# Sheet1.net
KiCad netlist of a schematic drawn in Altium Designer
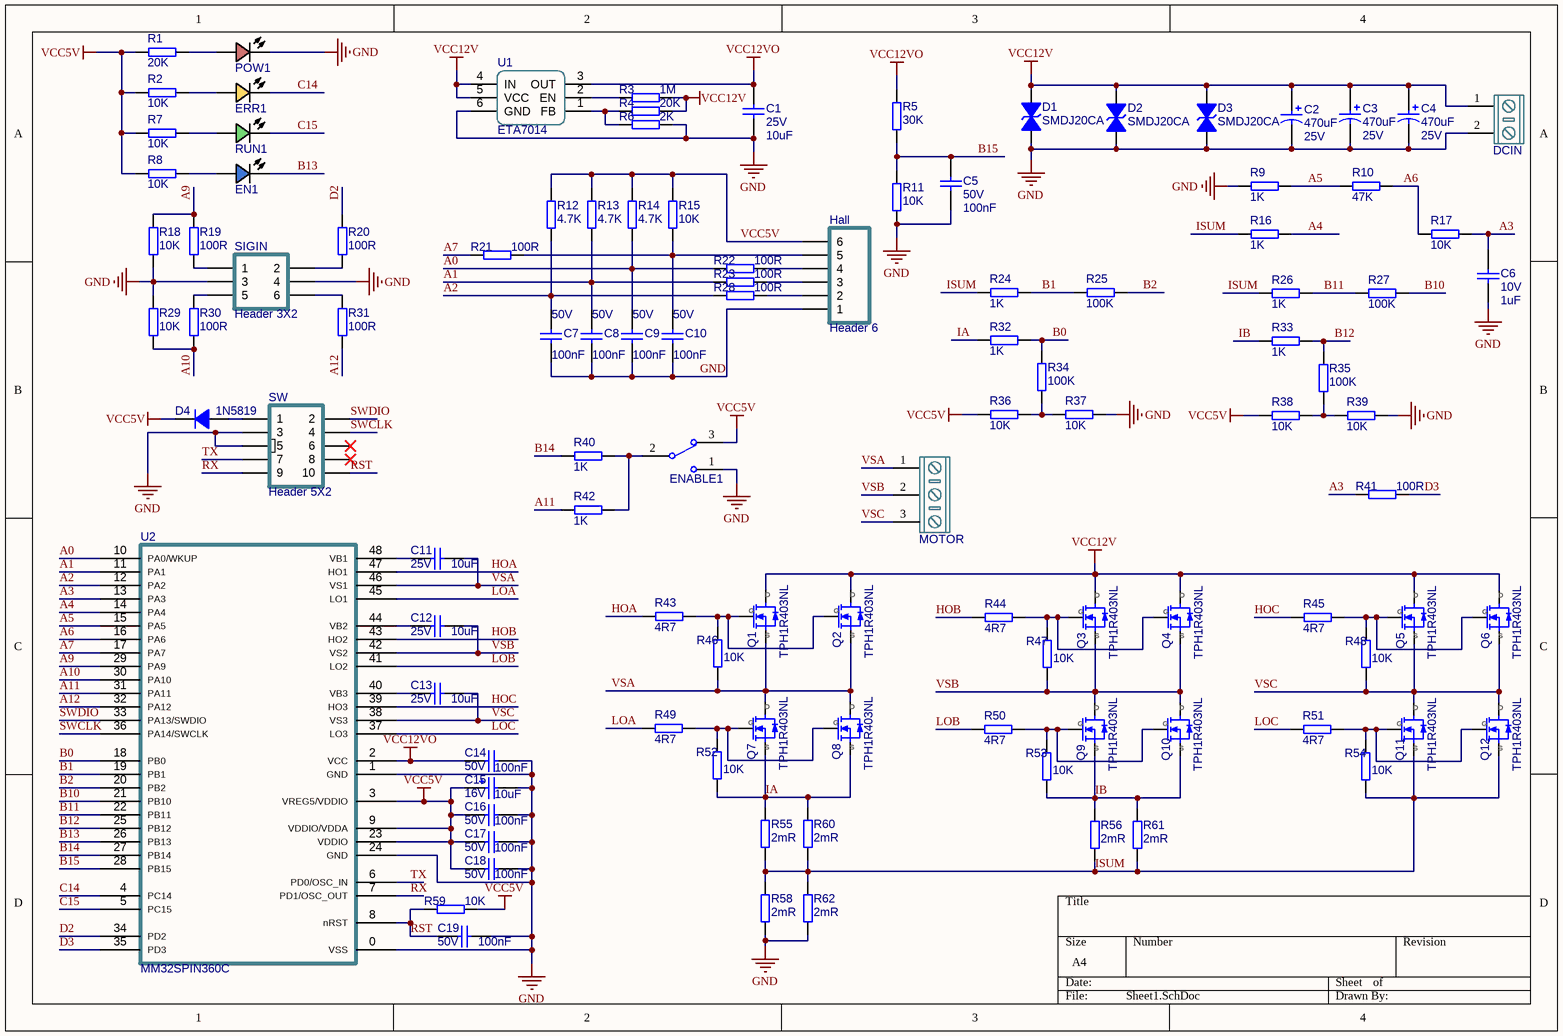
[diagram p0: Sheet1.SchDoc]

(export (version "E")
  (design (tool "Eeschema 10.0.6"))
  (components
    (comp (ref "C1")
      (value "10uF")
      (footprint "CAPC2012[0805]S-N")
      (description "贴片电容")
      (fields
        (field (name "TOLERANCE") "±10%")
        (field (name "VOLTAGE") "25V")
        (field (name "Comment") "10uF ±10% 25V")
      )
      (libsource (lib "无刷电调-MindMotion") (part "Cap-Chip"))
    )
    (comp (ref "C2")
      (value "470uF")
      (footprint "CAPPR3.5-8X12")
      (description "Polarized Capacitor (Radial)")
      (fields
        (field (name "VOLTAGE") "25V")
        (field (name "Comment") "470uF 25V")
        (field (name "PUBLISHER") "Altium Limited")
      )
      (libsource (lib "无刷电调-MindMotion") (part "Cap-Elect"))
    )
    (comp (ref "C3")
      (value "470uF")
      (footprint "CAPPR3.5-8X12")
      (description "Polarized Capacitor (Radial)")
      (fields
        (field (name "VOLTAGE") "25V")
        (field (name "Comment") "470uF 25V")
        (field (name "PUBLISHER") "Altium Limited")
      )
      (libsource (lib "无刷电调-MindMotion") (part "Cap-Elect"))
    )
    (comp (ref "C4")
      (value "470uF")
      (footprint "CAPPR3.5-8X12")
      (description "Polarized Capacitor (Radial)")
      (fields
        (field (name "VOLTAGE") "25V")
        (field (name "Comment") "470uF 25V")
        (field (name "PUBLISHER") "Altium Limited")
      )
      (libsource (lib "无刷电调-MindMotion") (part "Cap-Elect"))
    )
    (comp (ref "C5")
      (value "100nF")
      (footprint "CAPC2012[0805]S-N")
      (description "贴片电容")
      (fields
        (field (name "TOLERANCE") "±10%")
        (field (name "VOLTAGE") "50V")
        (field (name "Comment") "100nF ±10% 50V")
      )
      (libsource (lib "无刷电调-MindMotion") (part "Cap-Chip_1"))
    )
    (comp (ref "C6")
      (value "1uF")
      (footprint "CAPC2012[0805]S-N")
      (description "贴片电容")
      (fields
        (field (name "TOLERANCE") "±10%")
        (field (name "VOLTAGE") "10V")
        (field (name "Comment") "1uF ±10% 10V")
      )
      (libsource (lib "无刷电调-MindMotion") (part "Cap-Chip_2"))
    )
    (comp (ref "C7")
      (value "100nF")
      (footprint "CAPC2012[0805]S-N")
      (description "贴片电容")
      (fields
        (field (name "TOLERANCE") "±10%")
        (field (name "VOLTAGE") "50V")
        (field (name "Comment") "100nF ±10% 50V")
      )
      (libsource (lib "无刷电调-MindMotion") (part "Cap-Chip_1"))
    )
    (comp (ref "C8")
      (value "100nF")
      (footprint "CAPC2012[0805]S-N")
      (description "贴片电容")
      (fields
        (field (name "TOLERANCE") "±10%")
        (field (name "VOLTAGE") "50V")
        (field (name "Comment") "100nF ±10% 50V")
      )
      (libsource (lib "无刷电调-MindMotion") (part "Cap-Chip_1"))
    )
    (comp (ref "C9")
      (value "100nF")
      (footprint "CAPC2012[0805]S-N")
      (description "贴片电容")
      (fields
        (field (name "TOLERANCE") "±10%")
        (field (name "VOLTAGE") "50V")
        (field (name "Comment") "100nF ±10% 50V")
      )
      (libsource (lib "无刷电调-MindMotion") (part "Cap-Chip_1"))
    )
    (comp (ref "C10")
      (value "100nF")
      (footprint "CAPC2012[0805]S-N")
      (description "贴片电容")
      (fields
        (field (name "TOLERANCE") "±10%")
        (field (name "VOLTAGE") "50V")
        (field (name "Comment") "100nF ±10% 50V")
      )
      (libsource (lib "无刷电调-MindMotion") (part "Cap-Chip_1"))
    )
    (comp (ref "C11")
      (value "10uF")
      (footprint "CAPC2012[0805]S-N")
      (description "贴片电容")
      (fields
        (field (name "TOLERANCE") "±10%")
        (field (name "VOLTAGE") "25V")
        (field (name "Comment") "10uF ±10% 25V")
      )
      (libsource (lib "无刷电调-MindMotion") (part "Cap-Chip"))
    )
    (comp (ref "C12")
      (value "10uF")
      (footprint "CAPC2012[0805]S-N")
      (description "贴片电容")
      (fields
        (field (name "TOLERANCE") "±10%")
        (field (name "VOLTAGE") "25V")
        (field (name "Comment") "10uF ±10% 25V")
      )
      (libsource (lib "无刷电调-MindMotion") (part "Cap-Chip"))
    )
    (comp (ref "C13")
      (value "10uF")
      (footprint "CAPC2012[0805]S-N")
      (description "贴片电容")
      (fields
        (field (name "TOLERANCE") "±10%")
        (field (name "VOLTAGE") "25V")
        (field (name "Comment") "10uF ±10% 25V")
      )
      (libsource (lib "无刷电调-MindMotion") (part "Cap-Chip"))
    )
    (comp (ref "C14")
      (value "100nF")
      (footprint "CAPC2012[0805]S-N")
      (description "贴片电容")
      (fields
        (field (name "TOLERANCE") "±10%")
        (field (name "VOLTAGE") "50V")
        (field (name "Comment") "100nF ±10% 50V")
      )
      (libsource (lib "无刷电调-MindMotion") (part "Cap-Chip_1"))
    )
    (comp (ref "C15")
      (value "10uF")
      (footprint "CAPT3216")
      (description "Tantalum Capacitor")
      (fields
        (field (name "VOLTAGE") "16V")
        (field (name "Comment") "10uF 16V")
        (field (name "PUBLISHER") "Altium Limited")
      )
      (libsource (lib "无刷电调-MindMotion") (part "Cap-Tan"))
    )
    (comp (ref "C16")
      (value "100nF")
      (footprint "CAPC2012[0805]S-N")
      (description "贴片电容")
      (fields
        (field (name "TOLERANCE") "±10%")
        (field (name "VOLTAGE") "50V")
        (field (name "Comment") "100nF ±10% 50V")
      )
      (libsource (lib "无刷电调-MindMotion") (part "Cap-Chip_1"))
    )
    (comp (ref "C17")
      (value "100nF")
      (footprint "CAPC2012[0805]S-N")
      (description "贴片电容")
      (fields
        (field (name "TOLERANCE") "±10%")
        (field (name "VOLTAGE") "50V")
        (field (name "Comment") "100nF ±10% 50V")
      )
      (libsource (lib "无刷电调-MindMotion") (part "Cap-Chip_1"))
    )
    (comp (ref "C18")
      (value "100nF")
      (footprint "CAPC2012[0805]S-N")
      (description "贴片电容")
      (fields
        (field (name "TOLERANCE") "±10%")
        (field (name "VOLTAGE") "50V")
        (field (name "Comment") "100nF ±10% 50V")
      )
      (libsource (lib "无刷电调-MindMotion") (part "Cap-Chip_1"))
    )
    (comp (ref "C19")
      (value "100nF")
      (footprint "CAPC2012[0805]S-N")
      (description "贴片电容")
      (fields
        (field (name "TOLERANCE") "±10%")
        (field (name "VOLTAGE") "50V")
        (field (name "Comment") "100nF ±10% 50V")
      )
      (libsource (lib "无刷电调-MindMotion") (part "Cap-Chip_1"))
    )
    (comp (ref "D1")
      (value "SMDJ20CA")
      (footprint "SMC[DO-214AB]")
      (description "TRANSIENT VOLTAGE  SUPPRESSOR DIODE")
      (fields (field (name "PUBLISHER") "Altium Limited"))
      (libsource (lib "无刷电调-MindMotion") (part "Diode TVS Bi-Dir"))
    )
    (comp (ref "D2")
      (value "SMDJ20CA")
      (footprint "SMC[DO-214AB]")
      (description "TRANSIENT VOLTAGE  SUPPRESSOR DIODE")
      (fields (field (name "PUBLISHER") "Altium Limited"))
      (libsource (lib "无刷电调-MindMotion") (part "Diode TVS Bi-Dir"))
    )
    (comp (ref "D3")
      (value "SMDJ20CA")
      (footprint "SMC[DO-214AB]")
      (description "TRANSIENT VOLTAGE  SUPPRESSOR DIODE")
      (fields (field (name "PUBLISHER") "Altium Limited"))
      (libsource (lib "无刷电调-MindMotion") (part "Diode TVS Bi-Dir"))
    )
    (comp (ref "D4")
      (value "1N5819")
      (footprint "SOD-123-L")
      (description "普通二极管 Diode")
      (fields (field (name "PUBLISHER") "Altium Limited"))
      (libsource (lib "无刷电调-MindMotion") (part "Diode"))
    )
    (comp (ref "DCIN")
      (value "KF/WJ/DG 30x connecter")
      (footprint "KF/WJ/DG 301-2p-5.0mm")
      (description "接线端子 2Pin")
      (libsource (lib "无刷电调-MindMotion") (part "KF/WJ/DG 30x"))
    )
    (comp (ref "EN1")
      (value "蓝色贴片LED")
      (footprint "CAPC2012[0805]S-N")
      (fields (field (name "PUBLISHER") "Altium Limited"))
      (libsource (lib "无刷电调-MindMotion") (part "LED Chip Blue"))
    )
    (comp (ref "ENABLE1")
      (value "SW-SPDT")
      (footprint "SS12D10")
      (description "单刀双掷开关 3脚船型、钮子、拨动开关 SPDT Subminiature Toggle Switch")
      (fields (field (name "PUBLISHER") "Altium Limited"))
      (libsource (lib "无刷电调-MindMotion") (part "SW-SPDT"))
    )
    (comp (ref "ERR1")
      (value "黄色贴片LED")
      (footprint "CAPC2012[0805]S-N")
      (fields (field (name "PUBLISHER") "Altium Limited"))
      (libsource (lib "无刷电调-MindMotion") (part "LED Chip Yellow"))
    )
    (comp (ref "Hall")
      (value "Header 6")
      (footprint "ZH1.5-WF-6P")
      (description "Header, 6-Pin")
      (fields (field (name "PUBLISHER") "Altium Limited"))
      (libsource (lib "无刷电调-MindMotion") (part "Header 6"))
    )
    (comp (ref "MOTOR")
      (value "KF/WJ/DG 30x connecter")
      (footprint "KF/WJ/DG 301-3p-5.0mm")
      (description "接线端子 3Pin")
      (libsource (lib "无刷电调-MindMotion") (part "KF/WJ/DG 30x-3P"))
    )
    (comp (ref "POW1")
      (value "红色贴片LED")
      (footprint "CAPC2012[0805]S-N")
      (fields (field (name "PUBLISHER") "Altium Limited"))
      (libsource (lib "无刷电调-MindMotion") (part "LED Chip Red"))
    )
    (comp (ref "Q1")
      (value "TPH1R403NL")
      (footprint "DFN5x6")
      (description "东芝 N沟 MOS")
      (libsource (lib "无刷电调-MindMotion") (part "TPH1R403NL"))
    )
    (comp (ref "Q2")
      (value "TPH1R403NL")
      (footprint "DFN5x6")
      (description "东芝 N沟 MOS")
      (libsource (lib "无刷电调-MindMotion") (part "TPH1R403NL"))
    )
    (comp (ref "Q3")
      (value "TPH1R403NL")
      (footprint "DFN5x6")
      (description "东芝 N沟 MOS")
      (libsource (lib "无刷电调-MindMotion") (part "TPH1R403NL"))
    )
    (comp (ref "Q4")
      (value "TPH1R403NL")
      (footprint "DFN5x6")
      (description "东芝 N沟 MOS")
      (libsource (lib "无刷电调-MindMotion") (part "TPH1R403NL"))
    )
    (comp (ref "Q5")
      (value "TPH1R403NL")
      (footprint "DFN5x6")
      (description "东芝 N沟 MOS")
      (libsource (lib "无刷电调-MindMotion") (part "TPH1R403NL"))
    )
    (comp (ref "Q6")
      (value "TPH1R403NL")
      (footprint "DFN5x6")
      (description "东芝 N沟 MOS")
      (libsource (lib "无刷电调-MindMotion") (part "TPH1R403NL"))
    )
    (comp (ref "Q7")
      (value "TPH1R403NL")
      (footprint "DFN5x6")
      (description "东芝 N沟 MOS")
      (libsource (lib "无刷电调-MindMotion") (part "TPH1R403NL"))
    )
    (comp (ref "Q8")
      (value "TPH1R403NL")
      (footprint "DFN5x6")
      (description "东芝 N沟 MOS")
      (libsource (lib "无刷电调-MindMotion") (part "TPH1R403NL"))
    )
    (comp (ref "Q9")
      (value "TPH1R403NL")
      (footprint "DFN5x6")
      (description "东芝 N沟 MOS")
      (libsource (lib "无刷电调-MindMotion") (part "TPH1R403NL"))
    )
    (comp (ref "Q10")
      (value "TPH1R403NL")
      (footprint "DFN5x6")
      (description "东芝 N沟 MOS")
      (libsource (lib "无刷电调-MindMotion") (part "TPH1R403NL"))
    )
    (comp (ref "Q11")
      (value "TPH1R403NL")
      (footprint "DFN5x6")
      (description "东芝 N沟 MOS")
      (libsource (lib "无刷电调-MindMotion") (part "TPH1R403NL"))
    )
    (comp (ref "Q12")
      (value "TPH1R403NL")
      (footprint "DFN5x6")
      (description "东芝 N沟 MOS")
      (libsource (lib "无刷电调-MindMotion") (part "TPH1R403NL"))
    )
    (comp (ref "R1")
      (value "20K")
      (footprint "CAPC2012[0805]S-N")
      (description "贴片电阻")
      (fields (field (name "TOLERANCE") "±1%") (field (name "Comment") "20K ±1%"))
      (libsource (lib "无刷电调-MindMotion") (part "Res-Chip_2"))
    )
    (comp (ref "R2")
      (value "10K")
      (footprint "CAPC2012[0805]S-N")
      (description "贴片电阻")
      (fields (field (name "TOLERANCE") "±1%") (field (name "Comment") "10K ±1%"))
      (libsource (lib "无刷电调-MindMotion") (part "Res-Chip"))
    )
    (comp (ref "R3")
      (value "1M")
      (footprint "CAPC2012[0805]S-N")
      (description "贴片电阻")
      (fields (field (name "TOLERANCE") "±1%") (field (name "Comment") "1M ±1%"))
      (libsource (lib "无刷电调-MindMotion") (part "Res-Chip_6"))
    )
    (comp (ref "R4")
      (value "20K")
      (footprint "CAPC2012[0805]S-N")
      (description "贴片电阻")
      (fields (field (name "TOLERANCE") "±1%") (field (name "Comment") "20K ±1%"))
      (libsource (lib "无刷电调-MindMotion") (part "Res-Chip_2"))
    )
    (comp (ref "R5")
      (value "30K")
      (footprint "CAPC2012[0805]S-N")
      (description "贴片电阻")
      (fields (field (name "TOLERANCE") "±1%") (field (name "Comment") "30K ±1%"))
      (libsource (lib "无刷电调-MindMotion") (part "Res-Chip_1"))
    )
    (comp (ref "R6")
      (value "2K")
      (footprint "CAPC2012[0805]S-N")
      (description "贴片电阻")
      (fields (field (name "TOLERANCE") "±1%") (field (name "Comment") "2K ±1%"))
      (libsource (lib "无刷电调-MindMotion") (part "Res-Chip_9"))
    )
    (comp (ref "R7")
      (value "10K")
      (footprint "CAPC2012[0805]S-N")
      (description "贴片电阻")
      (fields (field (name "TOLERANCE") "±1%") (field (name "Comment") "10K ±1%"))
      (libsource (lib "无刷电调-MindMotion") (part "Res-Chip"))
    )
    (comp (ref "R8")
      (value "10K")
      (footprint "CAPC2012[0805]S-N")
      (description "贴片电阻")
      (fields (field (name "TOLERANCE") "±1%") (field (name "Comment") "10K ±1%"))
      (libsource (lib "无刷电调-MindMotion") (part "Res-Chip"))
    )
    (comp (ref "R9")
      (value "1K")
      (footprint "CAPC2012[0805]S-N")
      (description "贴片电阻")
      (fields (field (name "TOLERANCE") "±1%") (field (name "Comment") "1K ±1%"))
      (libsource (lib "无刷电调-MindMotion") (part "Res-Chip_3"))
    )
    (comp (ref "R10")
      (value "47K")
      (footprint "CAPC2012[0805]S-N")
      (description "贴片电阻")
      (fields (field (name "TOLERANCE") "±1%") (field (name "Comment") "47K ±1%"))
      (libsource (lib "无刷电调-MindMotion") (part "Res-Chip_4"))
    )
    (comp (ref "R11")
      (value "10K")
      (footprint "CAPC2012[0805]S-N")
      (description "贴片电阻")
      (fields (field (name "TOLERANCE") "±1%") (field (name "Comment") "10K ±1%"))
      (libsource (lib "无刷电调-MindMotion") (part "Res-Chip"))
    )
    (comp (ref "R12")
      (value "4.7K")
      (footprint "CAPC2012[0805]S-N")
      (description "贴片电阻")
      (fields (field (name "TOLERANCE") "±1%") (field (name "Comment") "4.7K ±1%"))
      (libsource (lib "无刷电调-MindMotion") (part "Res-Chip_7"))
    )
    (comp (ref "R13")
      (value "4.7K")
      (footprint "CAPC2012[0805]S-N")
      (description "贴片电阻")
      (fields (field (name "TOLERANCE") "±1%") (field (name "Comment") "4.7K ±1%"))
      (libsource (lib "无刷电调-MindMotion") (part "Res-Chip_7"))
    )
    (comp (ref "R14")
      (value "4.7K")
      (footprint "CAPC2012[0805]S-N")
      (description "贴片电阻")
      (fields (field (name "TOLERANCE") "±1%") (field (name "Comment") "4.7K ±1%"))
      (libsource (lib "无刷电调-MindMotion") (part "Res-Chip_7"))
    )
    (comp (ref "R15")
      (value "10K")
      (footprint "CAPC2012[0805]S-N")
      (description "贴片电阻")
      (fields (field (name "TOLERANCE") "±1%") (field (name "Comment") "10K ±1%"))
      (libsource (lib "无刷电调-MindMotion") (part "Res-Chip_7"))
    )
    (comp (ref "R16")
      (value "1K")
      (footprint "CAPC2012[0805]S-N")
      (description "贴片电阻")
      (fields (field (name "TOLERANCE") "±1%") (field (name "Comment") "1K ±1%"))
      (libsource (lib "无刷电调-MindMotion") (part "Res-Chip_3"))
    )
    (comp (ref "R17")
      (value "10K")
      (footprint "CAPC2012[0805]S-N")
      (description "贴片电阻")
      (fields (field (name "TOLERANCE") "±1%") (field (name "Comment") "10K ±1%"))
      (libsource (lib "无刷电调-MindMotion") (part "Res-Chip"))
    )
    (comp (ref "R18")
      (value "10K")
      (footprint "CAPC2012[0805]S-N")
      (description "贴片电阻")
      (fields (field (name "TOLERANCE") "±1%") (field (name "Comment") "10K ±1%"))
      (libsource (lib "无刷电调-MindMotion") (part "Res-Chip"))
    )
    (comp (ref "R19")
      (value "100R")
      (footprint "CAPC2012[0805]S-N")
      (description "贴片电阻")
      (fields (field (name "TOLERANCE") "±1%") (field (name "Comment") "100R ±1%"))
      (libsource (lib "无刷电调-MindMotion") (part "Res-Chip_8"))
    )
    (comp (ref "R20")
      (value "100R")
      (footprint "CAPC2012[0805]S-N")
      (description "贴片电阻")
      (fields (field (name "TOLERANCE") "±1%") (field (name "Comment") "100R ±1%"))
      (libsource (lib "无刷电调-MindMotion") (part "Res-Chip_8"))
    )
    (comp (ref "R21")
      (value "100R")
      (footprint "CAPC2012[0805]S-N")
      (description "贴片电阻")
      (fields (field (name "TOLERANCE") "±1%") (field (name "Comment") "100R ±1%"))
      (libsource (lib "无刷电调-MindMotion") (part "Res-Chip_8"))
    )
    (comp (ref "R22")
      (value "100R")
      (footprint "CAPC2012[0805]S-N")
      (description "贴片电阻")
      (fields (field (name "TOLERANCE") "±1%") (field (name "Comment") "100R ±1%"))
      (libsource (lib "无刷电调-MindMotion") (part "Res-Chip_8"))
    )
    (comp (ref "R23")
      (value "100R")
      (footprint "CAPC2012[0805]S-N")
      (description "贴片电阻")
      (fields (field (name "TOLERANCE") "±1%") (field (name "Comment") "100R ±1%"))
      (libsource (lib "无刷电调-MindMotion") (part "Res-Chip_8"))
    )
    (comp (ref "R24")
      (value "1K")
      (footprint "CAPC2012[0805]S-N")
      (description "贴片电阻")
      (fields (field (name "TOLERANCE") "±1%") (field (name "Comment") "1K ±1%"))
      (libsource (lib "无刷电调-MindMotion") (part "Res-Chip_3"))
    )
    (comp (ref "R25")
      (value "100K")
      (footprint "CAPC2012[0805]S-N")
      (description "贴片电阻")
      (fields (field (name "TOLERANCE") "±1%") (field (name "Comment") "100K ±1%"))
      (libsource (lib "无刷电调-MindMotion") (part "Res-Chip_5"))
    )
    (comp (ref "R26")
      (value "1K")
      (footprint "CAPC2012[0805]S-N")
      (description "贴片电阻")
      (fields (field (name "TOLERANCE") "±1%") (field (name "Comment") "1K ±1%"))
      (libsource (lib "无刷电调-MindMotion") (part "Res-Chip_3"))
    )
    (comp (ref "R27")
      (value "100K")
      (footprint "CAPC2012[0805]S-N")
      (description "贴片电阻")
      (fields (field (name "TOLERANCE") "±1%") (field (name "Comment") "100K ±1%"))
      (libsource (lib "无刷电调-MindMotion") (part "Res-Chip_5"))
    )
    (comp (ref "R28")
      (value "100R")
      (footprint "CAPC2012[0805]S-N")
      (description "贴片电阻")
      (fields (field (name "TOLERANCE") "±1%") (field (name "Comment") "100R ±1%"))
      (libsource (lib "无刷电调-MindMotion") (part "Res-Chip_8"))
    )
    (comp (ref "R29")
      (value "10K")
      (footprint "CAPC2012[0805]S-N")
      (description "贴片电阻")
      (fields (field (name "TOLERANCE") "±1%") (field (name "Comment") "10K ±1%"))
      (libsource (lib "无刷电调-MindMotion") (part "Res-Chip"))
    )
    (comp (ref "R30")
      (value "100R")
      (footprint "CAPC2012[0805]S-N")
      (description "贴片电阻")
      (fields (field (name "TOLERANCE") "±1%") (field (name "Comment") "100R ±1%"))
      (libsource (lib "无刷电调-MindMotion") (part "Res-Chip_8"))
    )
    (comp (ref "R31")
      (value "100R")
      (footprint "CAPC2012[0805]S-N")
      (description "贴片电阻")
      (fields (field (name "TOLERANCE") "±1%") (field (name "Comment") "100R ±1%"))
      (libsource (lib "无刷电调-MindMotion") (part "Res-Chip_8"))
    )
    (comp (ref "R32")
      (value "1K")
      (footprint "CAPC2012[0805]S-N")
      (description "贴片电阻")
      (fields (field (name "TOLERANCE") "±1%") (field (name "Comment") "1K ±1%"))
      (libsource (lib "无刷电调-MindMotion") (part "Res-Chip_3"))
    )
    (comp (ref "R33")
      (value "1K")
      (footprint "CAPC2012[0805]S-N")
      (description "贴片电阻")
      (fields (field (name "TOLERANCE") "±1%") (field (name "Comment") "1K ±1%"))
      (libsource (lib "无刷电调-MindMotion") (part "Res-Chip_3"))
    )
    (comp (ref "R34")
      (value "100K")
      (footprint "CAPC2012[0805]S-N")
      (description "贴片电阻")
      (fields (field (name "TOLERANCE") "±1%") (field (name "Comment") "100K ±1%"))
      (libsource (lib "无刷电调-MindMotion") (part "Res-Chip_5"))
    )
    (comp (ref "R35")
      (value "100K")
      (footprint "CAPC2012[0805]S-N")
      (description "贴片电阻")
      (fields (field (name "TOLERANCE") "±1%") (field (name "Comment") "100K ±1%"))
      (libsource (lib "无刷电调-MindMotion") (part "Res-Chip_5"))
    )
    (comp (ref "R36")
      (value "10K")
      (footprint "CAPC2012[0805]S-N")
      (description "贴片电阻")
      (fields (field (name "TOLERANCE") "±1%") (field (name "Comment") "10K ±1%"))
      (libsource (lib "无刷电调-MindMotion") (part "Res-Chip"))
    )
    (comp (ref "R37")
      (value "10K")
      (footprint "CAPC2012[0805]S-N")
      (description "贴片电阻")
      (fields (field (name "TOLERANCE") "±1%") (field (name "Comment") "10K ±1%"))
      (libsource (lib "无刷电调-MindMotion") (part "Res-Chip"))
    )
    (comp (ref "R38")
      (value "10K")
      (footprint "CAPC2012[0805]S-N")
      (description "贴片电阻")
      (fields (field (name "TOLERANCE") "±1%") (field (name "Comment") "10K ±1%"))
      (libsource (lib "无刷电调-MindMotion") (part "Res-Chip"))
    )
    (comp (ref "R39")
      (value "10K")
      (footprint "CAPC2012[0805]S-N")
      (description "贴片电阻")
      (fields (field (name "TOLERANCE") "±1%") (field (name "Comment") "10K ±1%"))
      (libsource (lib "无刷电调-MindMotion") (part "Res-Chip"))
    )
    (comp (ref "R40")
      (value "1K")
      (footprint "CAPC2012[0805]S-N")
      (description "贴片电阻")
      (fields (field (name "TOLERANCE") "±1%") (field (name "Comment") "1K ±1%"))
      (libsource (lib "无刷电调-MindMotion") (part "Res-Chip_3"))
    )
    (comp (ref "R41")
      (value "100R")
      (footprint "CAPC2012[0805]S-N")
      (description "贴片电阻")
      (fields (field (name "TOLERANCE") "±1%") (field (name "Comment") "100R ±1%"))
      (libsource (lib "无刷电调-MindMotion") (part "Res-Chip_8"))
    )
    (comp (ref "R42")
      (value "1K")
      (footprint "CAPC2012[0805]S-N")
      (description "贴片电阻")
      (fields (field (name "TOLERANCE") "±1%") (field (name "Comment") "1K ±1%"))
      (libsource (lib "无刷电调-MindMotion") (part "Res-Chip_3"))
    )
    (comp (ref "R43")
      (value "4R7")
      (footprint "CAPC2012[0805]S-N")
      (description "贴片电阻")
      (fields (field (name "TOLERANCE") "±1%") (field (name "Comment") "4R7 ±1%"))
      (libsource (lib "无刷电调-MindMotion") (part "Res-Chip_10"))
    )
    (comp (ref "R44")
      (value "4R7")
      (footprint "CAPC2012[0805]S-N")
      (description "贴片电阻")
      (fields (field (name "TOLERANCE") "±1%") (field (name "Comment") "4R7 ±1%"))
      (libsource (lib "无刷电调-MindMotion") (part "Res-Chip_10"))
    )
    (comp (ref "R45")
      (value "4R7")
      (footprint "CAPC2012[0805]S-N")
      (description "贴片电阻")
      (fields (field (name "TOLERANCE") "±1%") (field (name "Comment") "4R7 ±1%"))
      (libsource (lib "无刷电调-MindMotion") (part "Res-Chip_10"))
    )
    (comp (ref "R46")
      (value "10K")
      (footprint "CAPC2012[0805]S-N")
      (description "贴片电阻")
      (fields (field (name "TOLERANCE") "±1%") (field (name "Comment") "10K ±1%"))
      (libsource (lib "无刷电调-MindMotion") (part "Res-Chip"))
    )
    (comp (ref "R47")
      (value "10K")
      (footprint "CAPC2012[0805]S-N")
      (description "贴片电阻")
      (fields (field (name "TOLERANCE") "±1%") (field (name "Comment") "10K ±1%"))
      (libsource (lib "无刷电调-MindMotion") (part "Res-Chip"))
    )
    (comp (ref "R48")
      (value "10K")
      (footprint "CAPC2012[0805]S-N")
      (description "贴片电阻")
      (fields (field (name "TOLERANCE") "±1%") (field (name "Comment") "10K ±1%"))
      (libsource (lib "无刷电调-MindMotion") (part "Res-Chip"))
    )
    (comp (ref "R49")
      (value "4R7")
      (footprint "CAPC2012[0805]S-N")
      (description "贴片电阻")
      (fields (field (name "TOLERANCE") "±1%") (field (name "Comment") "4R7 ±1%"))
      (libsource (lib "无刷电调-MindMotion") (part "Res-Chip_10"))
    )
    (comp (ref "R50")
      (value "4R7")
      (footprint "CAPC2012[0805]S-N")
      (description "贴片电阻")
      (fields (field (name "TOLERANCE") "±1%") (field (name "Comment") "4R7 ±1%"))
      (libsource (lib "无刷电调-MindMotion") (part "Res-Chip_10"))
    )
    (comp (ref "R51")
      (value "4R7")
      (footprint "CAPC2012[0805]S-N")
      (description "贴片电阻")
      (fields (field (name "TOLERANCE") "±1%") (field (name "Comment") "4R7 ±1%"))
      (libsource (lib "无刷电调-MindMotion") (part "Res-Chip_10"))
    )
    (comp (ref "R52")
      (value "10K")
      (footprint "CAPC2012[0805]S-N")
      (description "贴片电阻")
      (fields (field (name "TOLERANCE") "±1%") (field (name "Comment") "10K ±1%"))
      (libsource (lib "无刷电调-MindMotion") (part "Res-Chip"))
    )
    (comp (ref "R53")
      (value "10K")
      (footprint "CAPC2012[0805]S-N")
      (description "贴片电阻")
      (fields (field (name "TOLERANCE") "±1%") (field (name "Comment") "10K ±1%"))
      (libsource (lib "无刷电调-MindMotion") (part "Res-Chip"))
    )
    (comp (ref "R54")
      (value "10K")
      (footprint "CAPC2012[0805]S-N")
      (description "贴片电阻")
      (fields (field (name "TOLERANCE") "±1%") (field (name "Comment") "10K ±1%"))
      (libsource (lib "无刷电调-MindMotion") (part "Res-Chip"))
    )
    (comp (ref "R55")
      (value "2mR")
      (footprint "RESC6332[2512]S")
      (description "贴片电阻")
      (fields (field (name "TOLERANCE") "±1%") (field (name "Comment") "2mR ±1%"))
      (libsource (lib "无刷电调-MindMotion") (part "Res-Chip_11"))
    )
    (comp (ref "R56")
      (value "2mR")
      (footprint "RESC6332[2512]S")
      (description "贴片电阻")
      (fields (field (name "TOLERANCE") "±1%") (field (name "Comment") "2mR ±1%"))
      (libsource (lib "无刷电调-MindMotion") (part "Res-Chip_11"))
    )
    (comp (ref "R58")
      (value "2mR")
      (footprint "RESC6332[2512]S")
      (description "贴片电阻")
      (fields (field (name "TOLERANCE") "±1%") (field (name "Comment") "2mR ±1%"))
      (libsource (lib "无刷电调-MindMotion") (part "Res-Chip_11"))
    )
    (comp (ref "R59")
      (value "10K")
      (footprint "CAPC2012[0805]S-N")
      (description "贴片电阻")
      (fields (field (name "TOLERANCE") "±1%") (field (name "Comment") "10K ±1%"))
      (libsource (lib "无刷电调-MindMotion") (part "Res-Chip"))
    )
    (comp (ref "R60")
      (value "2mR")
      (footprint "res2m")
      (description "贴片电阻")
      (fields (field (name "TOLERANCE") "±1%") (field (name "Comment") "2mR ±1%"))
      (libsource (lib "无刷电调-MindMotion") (part "Res-Chip_11"))
    )
    (comp (ref "R61")
      (value "2mR")
      (footprint "res2m")
      (description "贴片电阻")
      (fields (field (name "TOLERANCE") "±1%") (field (name "Comment") "2mR ±1%"))
      (libsource (lib "无刷电调-MindMotion") (part "Res-Chip_11"))
    )
    (comp (ref "R62")
      (value "2mR")
      (footprint "res2m")
      (description "贴片电阻")
      (fields (field (name "TOLERANCE") "±1%") (field (name "Comment") "2mR ±1%"))
      (libsource (lib "无刷电调-MindMotion") (part "Res-Chip_11"))
    )
    (comp (ref "RUN1")
      (value "翠绿贴片LED")
      (footprint "CAPC2012[0805]S-N")
      (fields (field (name "PUBLISHER") "Altium Limited"))
      (libsource (lib "无刷电调-MindMotion") (part "LED Chip Green"))
    )
    (comp (ref "SIGIN")
      (value "Header 3X2")
      (footprint "HDR2X3")
      (description "Header, 3-Pin, Dual row")
      (fields (field (name "PUBLISHER") "Altium Limited"))
      (libsource (lib "无刷电调-MindMotion") (part "Header 3X2"))
    )
    (comp (ref "SW")
      (value "Header 5X2")
      (footprint "HDR2X5")
      (description "Header, 5-Pin, Dual row")
      (fields (field (name "PUBLISHER") "Altium Limited"))
      (libsource (lib "无刷电调-MindMotion") (part "Header 5X2"))
    )
    (comp (ref "U1")
      (value "ETA7014")
      (footprint "SOT-23-6")
      (description "ETA7014 OVP芯片")
      (libsource (lib "无刷电调-MindMotion") (part "ETA7014"))
    )
    (comp (ref "U2")
      (value "MM32SPIN360C")
      (footprint "QFN48-6x6")
      (fields (field (name "PUBLISHER") "Altium Limited"))
      (libsource (lib "无刷电调-MindMotion") (part "MM32SPIN360C"))
    )
  )
  (nets
    (net (code "1") (name "/A0") (class "Default")
      (node (ref "C9") (pin "2") (pinfunction "2_2") (pintype "passive"))
      (node (ref "R14") (pin "1") (pinfunction "1_1") (pintype "passive"))
      (node (ref "R22") (pin "1") (pinfunction "1_1") (pintype "passive"))
      (node (ref "U2") (pin "10") (pinfunction "PA0/WKUP_10") (pintype "passive"))
    )
    (net (code "2") (name "/A1") (class "Default")
      (node (ref "C8") (pin "2") (pinfunction "2_2") (pintype "passive"))
      (node (ref "R13") (pin "1") (pinfunction "1_1") (pintype "passive"))
      (node (ref "R23") (pin "1") (pinfunction "1_1") (pintype "passive"))
      (node (ref "U2") (pin "11") (pinfunction "PA1_11") (pintype "passive"))
    )
    (net (code "3") (name "/A2") (class "Default")
      (node (ref "C7") (pin "2") (pinfunction "2_2") (pintype "passive"))
      (node (ref "R12") (pin "1") (pinfunction "1_1") (pintype "passive"))
      (node (ref "R28") (pin "1") (pinfunction "1_1") (pintype "passive"))
      (node (ref "U2") (pin "12") (pinfunction "PA2_12") (pintype "passive"))
    )
    (net (code "4") (name "/A3") (class "Default")
      (node (ref "C6") (pin "2") (pinfunction "2_2") (pintype "passive"))
      (node (ref "R17") (pin "2") (pinfunction "2_2") (pintype "passive"))
      (node (ref "R41") (pin "1") (pinfunction "1_1") (pintype "passive"))
      (node (ref "U2") (pin "13") (pinfunction "PA3_13") (pintype "passive"))
    )
    (net (code "5") (name "/A4") (class "Default")
      (node (ref "R16") (pin "2") (pinfunction "2_2") (pintype "passive"))
      (node (ref "U2") (pin "14") (pinfunction "PA4_14") (pintype "passive"))
    )
    (net (code "6") (name "/A5") (class "Default")
      (node (ref "R10") (pin "1") (pinfunction "1_1") (pintype "passive"))
      (node (ref "R9") (pin "2") (pinfunction "2_2") (pintype "passive"))
      (node (ref "U2") (pin "15") (pinfunction "PA5_15") (pintype "passive"))
    )
    (net (code "7") (name "/A6") (class "Default")
      (node (ref "R10") (pin "2") (pinfunction "2_2") (pintype "passive"))
      (node (ref "R17") (pin "1") (pinfunction "1_1") (pintype "passive"))
      (node (ref "U2") (pin "16") (pinfunction "PA6_16") (pintype "passive"))
    )
    (net (code "8") (name "/A7") (class "Default")
      (node (ref "R21") (pin "1") (pinfunction "1_1") (pintype "passive"))
      (node (ref "U2") (pin "17") (pinfunction "PA7_17") (pintype "passive"))
    )
    (net (code "9") (name "/A9") (class "Default")
      (node (ref "R18") (pin "2") (pinfunction "2_2") (pintype "passive"))
      (node (ref "R19") (pin "2") (pinfunction "2_2") (pintype "passive"))
      (node (ref "U2") (pin "29") (pinfunction "PA9_29") (pintype "passive"))
    )
    (net (code "10") (name "/A10") (class "Default")
      (node (ref "R29") (pin "1") (pinfunction "1_1") (pintype "passive"))
      (node (ref "R30") (pin "1") (pinfunction "1_1") (pintype "passive"))
      (node (ref "U2") (pin "30") (pinfunction "PA10_30") (pintype "passive"))
    )
    (net (code "11") (name "/A11") (class "Default")
      (node (ref "R42") (pin "1") (pinfunction "1_1") (pintype "passive"))
      (node (ref "U2") (pin "31") (pinfunction "PA11_31") (pintype "passive"))
    )
    (net (code "12") (name "/A12") (class "Default")
      (node (ref "R31") (pin "2") (pinfunction "2_2") (pintype "passive"))
      (node (ref "U2") (pin "32") (pinfunction "PA12_32") (pintype "passive"))
    )
    (net (code "13") (name "/B0") (class "Default")
      (node (ref "R32") (pin "2") (pinfunction "2_2") (pintype "passive"))
      (node (ref "R34") (pin "2") (pinfunction "2_2") (pintype "passive"))
      (node (ref "U2") (pin "18") (pinfunction "PB0_18") (pintype "passive"))
    )
    (net (code "14") (name "/B1") (class "Default")
      (node (ref "R24") (pin "2") (pinfunction "2_2") (pintype "passive"))
      (node (ref "R25") (pin "1") (pinfunction "1_1") (pintype "passive"))
      (node (ref "U2") (pin "19") (pinfunction "PB1_19") (pintype "passive"))
    )
    (net (code "15") (name "/B2") (class "Default")
      (node (ref "R25") (pin "2") (pinfunction "2_2") (pintype "passive"))
      (node (ref "U2") (pin "20") (pinfunction "PB2_20") (pintype "passive"))
    )
    (net (code "16") (name "/B10") (class "Default")
      (node (ref "R27") (pin "2") (pinfunction "2_2") (pintype "passive"))
      (node (ref "U2") (pin "21") (pinfunction "PB10_21") (pintype "passive"))
    )
    (net (code "17") (name "/B11") (class "Default")
      (node (ref "R26") (pin "2") (pinfunction "2_2") (pintype "passive"))
      (node (ref "R27") (pin "1") (pinfunction "1_1") (pintype "passive"))
      (node (ref "U2") (pin "22") (pinfunction "PB11_22") (pintype "passive"))
    )
    (net (code "18") (name "/B12") (class "Default")
      (node (ref "R33") (pin "2") (pinfunction "2_2") (pintype "passive"))
      (node (ref "R35") (pin "2") (pinfunction "2_2") (pintype "passive"))
      (node (ref "U2") (pin "25") (pinfunction "PB12_25") (pintype "passive"))
    )
    (net (code "19") (name "/B13") (class "Default")
      (node (ref "EN1") (pin "2") (pinfunction "2_2") (pintype "passive"))
      (node (ref "U2") (pin "26") (pinfunction "PB13_26") (pintype "passive"))
    )
    (net (code "20") (name "/B14") (class "Default")
      (node (ref "R40") (pin "1") (pinfunction "1_1") (pintype "passive"))
      (node (ref "U2") (pin "27") (pinfunction "PB14_27") (pintype "passive"))
    )
    (net (code "21") (name "/B15") (class "Default")
      (node (ref "C5") (pin "2") (pinfunction "2_2") (pintype "passive"))
      (node (ref "R11") (pin "2") (pinfunction "2_2") (pintype "passive"))
      (node (ref "R5") (pin "2") (pinfunction "2_2") (pintype "passive"))
      (node (ref "U2") (pin "28") (pinfunction "PB15_28") (pintype "passive"))
    )
    (net (code "22") (name "/C14") (class "Default")
      (node (ref "ERR1") (pin "2") (pinfunction "2_2") (pintype "passive"))
      (node (ref "U2") (pin "4") (pinfunction "PC14_4") (pintype "passive"))
    )
    (net (code "23") (name "/C15") (class "Default")
      (node (ref "RUN1") (pin "2") (pinfunction "2_2") (pintype "passive"))
      (node (ref "U2") (pin "5") (pinfunction "PC15_5") (pintype "passive"))
    )
    (net (code "24") (name "/D2") (class "Default")
      (node (ref "R20") (pin "2") (pinfunction "2_2") (pintype "passive"))
      (node (ref "U2") (pin "34") (pinfunction "PD2_34") (pintype "passive"))
    )
    (net (code "25") (name "/D3") (class "Default")
      (node (ref "R41") (pin "2") (pinfunction "2_2") (pintype "passive"))
      (node (ref "U2") (pin "35") (pinfunction "PD3_35") (pintype "passive"))
    )
    (net (code "26") (name "/HOA") (class "Default")
      (node (ref "R43") (pin "1") (pinfunction "1_1") (pintype "passive"))
      (node (ref "U2") (pin "47") (pinfunction "HO1_47") (pintype "passive"))
    )
    (net (code "27") (name "/HOB") (class "Default")
      (node (ref "R44") (pin "1") (pinfunction "1_1") (pintype "passive"))
      (node (ref "U2") (pin "43") (pinfunction "HO2_43") (pintype "passive"))
    )
    (net (code "28") (name "/HOC") (class "Default")
      (node (ref "R45") (pin "1") (pinfunction "1_1") (pintype "passive"))
      (node (ref "U2") (pin "39") (pinfunction "HO3_39") (pintype "passive"))
    )
    (net (code "29") (name "/IA") (class "Default")
      (node (ref "Q7") (pin "3") (pinfunction "S_3") (pintype "passive"))
      (node (ref "Q8") (pin "3") (pinfunction "S_3") (pintype "passive"))
      (node (ref "R32") (pin "1") (pinfunction "1_1") (pintype "passive"))
      (node (ref "R52") (pin "1") (pinfunction "1_1") (pintype "passive"))
      (node (ref "R55") (pin "2") (pinfunction "2_2") (pintype "passive"))
      (node (ref "R60") (pin "2") (pinfunction "2_2") (pintype "passive"))
    )
    (net (code "30") (name "/IB") (class "Default")
      (node (ref "Q10") (pin "3") (pinfunction "S_3") (pintype "passive"))
      (node (ref "Q9") (pin "3") (pinfunction "S_3") (pintype "passive"))
      (node (ref "R33") (pin "1") (pinfunction "1_1") (pintype "passive"))
      (node (ref "R53") (pin "1") (pinfunction "1_1") (pintype "passive"))
      (node (ref "R56") (pin "2") (pinfunction "2_2") (pintype "passive"))
      (node (ref "R61") (pin "2") (pinfunction "2_2") (pintype "passive"))
    )
    (net (code "31") (name "/ISUM") (class "Default")
      (node (ref "Q11") (pin "3") (pinfunction "S_3") (pintype "passive"))
      (node (ref "Q12") (pin "3") (pinfunction "S_3") (pintype "passive"))
      (node (ref "R16") (pin "1") (pinfunction "1_1") (pintype "passive"))
      (node (ref "R24") (pin "1") (pinfunction "1_1") (pintype "passive"))
      (node (ref "R26") (pin "1") (pinfunction "1_1") (pintype "passive"))
      (node (ref "R54") (pin "1") (pinfunction "1_1") (pintype "passive"))
      (node (ref "R55") (pin "1") (pinfunction "1_1") (pintype "passive"))
      (node (ref "R56") (pin "1") (pinfunction "1_1") (pintype "passive"))
      (node (ref "R58") (pin "2") (pinfunction "2_2") (pintype "passive"))
      (node (ref "R60") (pin "1") (pinfunction "1_1") (pintype "passive"))
      (node (ref "R61") (pin "1") (pinfunction "1_1") (pintype "passive"))
      (node (ref "R62") (pin "2") (pinfunction "2_2") (pintype "passive"))
    )
    (net (code "32") (name "/LOA") (class "Default")
      (node (ref "R49") (pin "1") (pinfunction "1_1") (pintype "passive"))
      (node (ref "U2") (pin "45") (pinfunction "LO1_45") (pintype "passive"))
    )
    (net (code "33") (name "/LOB") (class "Default")
      (node (ref "R50") (pin "1") (pinfunction "1_1") (pintype "passive"))
      (node (ref "U2") (pin "41") (pinfunction "LO2_41") (pintype "passive"))
    )
    (net (code "34") (name "/LOC") (class "Default")
      (node (ref "R51") (pin "1") (pinfunction "1_1") (pintype "passive"))
      (node (ref "U2") (pin "37") (pinfunction "LO3_37") (pintype "passive"))
    )
    (net (code "35") (name "/RST") (class "Default")
      (node (ref "C19") (pin "2") (pinfunction "2_2") (pintype "passive"))
      (node (ref "R59") (pin "1") (pinfunction "1_1") (pintype "passive"))
      (node (ref "SW") (pin "10") (pinfunction "10_10") (pintype "passive"))
      (node (ref "U2") (pin "8") (pinfunction "nRST_8") (pintype "passive"))
    )
    (net (code "36") (name "/RX") (class "Default")
      (node (ref "SW") (pin "9") (pinfunction "9_9") (pintype "passive"))
      (node (ref "U2") (pin "7") (pinfunction "PD1/OSC_OUT_7") (pintype "passive"))
    )
    (net (code "37") (name "/SWCLK") (class "Default")
      (node (ref "SW") (pin "4") (pinfunction "4_4") (pintype "passive"))
      (node (ref "U2") (pin "36") (pinfunction "PA14/SWCLK_36") (pintype "passive"))
    )
    (net (code "38") (name "/SWDIO") (class "Default")
      (node (ref "SW") (pin "2") (pinfunction "2_2") (pintype "passive"))
      (node (ref "U2") (pin "33") (pinfunction "PA13/SWDIO_33") (pintype "passive"))
    )
    (net (code "39") (name "/TX") (class "Default")
      (node (ref "SW") (pin "7") (pinfunction "7_7") (pintype "passive"))
      (node (ref "U2") (pin "6") (pinfunction "PD0/OSC_IN_6") (pintype "passive"))
    )
    (net (code "40") (name "/VSA") (class "Default")
      (node (ref "C11") (pin "2") (pinfunction "2_2") (pintype "passive"))
      (node (ref "MOTOR") (pin "1") (pinfunction "1_1") (pintype "passive"))
      (node (ref "Q1") (pin "3") (pinfunction "S_3") (pintype "passive"))
      (node (ref "Q2") (pin "3") (pinfunction "S_3") (pintype "passive"))
      (node (ref "Q7") (pin "1") (pinfunction "D_1") (pintype "passive"))
      (node (ref "Q8") (pin "1") (pinfunction "D_1") (pintype "passive"))
      (node (ref "R46") (pin "1") (pinfunction "1_1") (pintype "passive"))
      (node (ref "U2") (pin "46") (pinfunction "VS1_46") (pintype "passive"))
    )
    (net (code "41") (name "/VSB") (class "Default")
      (node (ref "C12") (pin "2") (pinfunction "2_2") (pintype "passive"))
      (node (ref "MOTOR") (pin "2") (pinfunction "2_2") (pintype "passive"))
      (node (ref "Q10") (pin "1") (pinfunction "D_1") (pintype "passive"))
      (node (ref "Q3") (pin "3") (pinfunction "S_3") (pintype "passive"))
      (node (ref "Q4") (pin "3") (pinfunction "S_3") (pintype "passive"))
      (node (ref "Q9") (pin "1") (pinfunction "D_1") (pintype "passive"))
      (node (ref "R47") (pin "1") (pinfunction "1_1") (pintype "passive"))
      (node (ref "U2") (pin "42") (pinfunction "VS2_42") (pintype "passive"))
    )
    (net (code "42") (name "/VSC") (class "Default")
      (node (ref "C13") (pin "2") (pinfunction "2_2") (pintype "passive"))
      (node (ref "MOTOR") (pin "3") (pinfunction "2_3") (pintype "passive"))
      (node (ref "Q11") (pin "1") (pinfunction "D_1") (pintype "passive"))
      (node (ref "Q12") (pin "1") (pinfunction "D_1") (pintype "passive"))
      (node (ref "Q5") (pin "3") (pinfunction "S_3") (pintype "passive"))
      (node (ref "Q6") (pin "3") (pinfunction "S_3") (pintype "passive"))
      (node (ref "R48") (pin "1") (pinfunction "1_1") (pintype "passive"))
      (node (ref "U2") (pin "38") (pinfunction "VS3_38") (pintype "passive"))
    )
    (net (code "43") (name "GND") (class "Default")
      (node (ref "C1") (pin "2") (pinfunction "2_2") (pintype "passive"))
      (node (ref "C10") (pin "1") (pinfunction "1_1") (pintype "passive"))
      (node (ref "C14") (pin "1") (pinfunction "1_1") (pintype "passive"))
      (node (ref "C15") (pin "2") (pinfunction "2_2") (pintype "passive"))
      (node (ref "C16") (pin "1") (pinfunction "1_1") (pintype "passive"))
      (node (ref "C17") (pin "1") (pinfunction "1_1") (pintype "passive"))
      (node (ref "C18") (pin "1") (pinfunction "1_1") (pintype "passive"))
      (node (ref "C19") (pin "1") (pinfunction "1_1") (pintype "passive"))
      (node (ref "C2") (pin "2") (pinfunction "2_2") (pintype "passive"))
      (node (ref "C3") (pin "2") (pinfunction "2_2") (pintype "passive"))
      (node (ref "C4") (pin "2") (pinfunction "2_2") (pintype "passive"))
      (node (ref "C5") (pin "1") (pinfunction "1_1") (pintype "passive"))
      (node (ref "C6") (pin "1") (pinfunction "1_1") (pintype "passive"))
      (node (ref "C7") (pin "1") (pinfunction "1_1") (pintype "passive"))
      (node (ref "C8") (pin "1") (pinfunction "1_1") (pintype "passive"))
      (node (ref "C9") (pin "1") (pinfunction "1_1") (pintype "passive"))
      (node (ref "D1") (pin "A") (pinfunction "A_A") (pintype "passive"))
      (node (ref "D2") (pin "A") (pinfunction "A_A") (pintype "passive"))
      (node (ref "D3") (pin "A") (pinfunction "A_A") (pintype "passive"))
      (node (ref "DCIN") (pin "2") (pinfunction "2_2") (pintype "passive"))
      (node (ref "ENABLE1") (pin "1") (pintype "passive"))
      (node (ref "Hall") (pin "1") (pinfunction "1_1") (pintype "passive"))
      (node (ref "POW1") (pin "2") (pinfunction "2_2") (pintype "passive"))
      (node (ref "R11") (pin "1") (pinfunction "1_1") (pintype "passive"))
      (node (ref "R18") (pin "1") (pinfunction "1_1") (pintype "passive"))
      (node (ref "R29") (pin "2") (pinfunction "2_2") (pintype "passive"))
      (node (ref "R37") (pin "2") (pinfunction "2_2") (pintype "passive"))
      (node (ref "R39") (pin "2") (pinfunction "2_2") (pintype "passive"))
      (node (ref "R58") (pin "1") (pinfunction "1_1") (pintype "passive"))
      (node (ref "R6") (pin "2") (pinfunction "2_2") (pintype "passive"))
      (node (ref "R62") (pin "1") (pinfunction "1_1") (pintype "passive"))
      (node (ref "R9") (pin "1") (pinfunction "1_1") (pintype "passive"))
      (node (ref "SIGIN") (pin "3") (pinfunction "3_3") (pintype "passive"))
      (node (ref "SIGIN") (pin "4") (pinfunction "4_4") (pintype "passive"))
      (node (ref "SW") (pin "3") (pinfunction "3_3") (pintype "passive"))
      (node (ref "SW") (pin "5") (pinfunction "5_5") (pintype "passive"))
      (node (ref "U1") (pin "6") (pinfunction "GND_6") (pintype "passive"))
      (node (ref "U2") (pin "0") (pinfunction "VSS_0") (pintype "passive"))
      (node (ref "U2") (pin "1") (pinfunction "GND_1") (pintype "passive"))
      (node (ref "U2") (pin "24") (pinfunction "GND_24") (pintype "passive"))
    )
    (net (code "44") (name "Net-(C10-Pad2)") (class "Default")
      (node (ref "C10") (pin "2") (pinfunction "2_2") (pintype "passive"))
      (node (ref "Hall") (pin "5") (pinfunction "5_5") (pintype "passive"))
      (node (ref "R15") (pin "1") (pinfunction "1_1") (pintype "passive"))
      (node (ref "R21") (pin "2") (pinfunction "2_2") (pintype "passive"))
    )
    (net (code "45") (name "Net-(D4-PadA)") (class "Default")
      (node (ref "D4") (pin "A") (pinfunction "A_A") (pintype "passive"))
      (node (ref "SW") (pin "1") (pinfunction "1_1") (pintype "passive"))
    )
    (net (code "46") (name "Net-(EN1-Pad1)") (class "Default")
      (node (ref "EN1") (pin "1") (pinfunction "1_1") (pintype "passive"))
      (node (ref "R8") (pin "2") (pinfunction "2_2") (pintype "passive"))
    )
    (net (code "47") (name "Net-(ENABLE1-Pad2)") (class "Default")
      (node (ref "ENABLE1") (pin "2") (pintype "passive"))
      (node (ref "R40") (pin "2") (pinfunction "2_2") (pintype "passive"))
      (node (ref "R42") (pin "2") (pinfunction "2_2") (pintype "passive"))
    )
    (net (code "48") (name "Net-(ERR1-Pad1)") (class "Default")
      (node (ref "ERR1") (pin "1") (pinfunction "1_1") (pintype "passive"))
      (node (ref "R2") (pin "2") (pinfunction "2_2") (pintype "passive"))
    )
    (net (code "49") (name "Net-(Hall-Pad2)") (class "Default")
      (node (ref "Hall") (pin "2") (pinfunction "2_2") (pintype "passive"))
      (node (ref "R28") (pin "2") (pinfunction "2_2") (pintype "passive"))
    )
    (net (code "50") (name "Net-(Hall-Pad3)") (class "Default")
      (node (ref "Hall") (pin "3") (pinfunction "3_3") (pintype "passive"))
      (node (ref "R23") (pin "2") (pinfunction "2_2") (pintype "passive"))
    )
    (net (code "51") (name "Net-(Hall-Pad4)") (class "Default")
      (node (ref "Hall") (pin "4") (pinfunction "4_4") (pintype "passive"))
      (node (ref "R22") (pin "2") (pinfunction "2_2") (pintype "passive"))
    )
    (net (code "52") (name "Net-(POW1-Pad1)") (class "Default")
      (node (ref "POW1") (pin "1") (pinfunction "1_1") (pintype "passive"))
      (node (ref "R1") (pin "2") (pinfunction "2_2") (pintype "passive"))
    )
    (net (code "53") (name "Net-(Q1-G)") (class "Default")
      (node (ref "Q1") (pin "2") (pinfunction "G_2") (pintype "passive"))
      (node (ref "Q2") (pin "2") (pinfunction "G_2") (pintype "passive"))
      (node (ref "R43") (pin "2") (pinfunction "2_2") (pintype "passive"))
      (node (ref "R46") (pin "2") (pinfunction "2_2") (pintype "passive"))
    )
    (net (code "54") (name "Net-(Q3-G)") (class "Default")
      (node (ref "Q3") (pin "2") (pinfunction "G_2") (pintype "passive"))
      (node (ref "Q4") (pin "2") (pinfunction "G_2") (pintype "passive"))
      (node (ref "R44") (pin "2") (pinfunction "2_2") (pintype "passive"))
      (node (ref "R47") (pin "2") (pinfunction "2_2") (pintype "passive"))
    )
    (net (code "55") (name "Net-(Q5-G)") (class "Default")
      (node (ref "Q5") (pin "2") (pinfunction "G_2") (pintype "passive"))
      (node (ref "Q6") (pin "2") (pinfunction "G_2") (pintype "passive"))
      (node (ref "R45") (pin "2") (pinfunction "2_2") (pintype "passive"))
      (node (ref "R48") (pin "2") (pinfunction "2_2") (pintype "passive"))
    )
    (net (code "56") (name "Net-(Q7-G)") (class "Default")
      (node (ref "Q7") (pin "2") (pinfunction "G_2") (pintype "passive"))
      (node (ref "Q8") (pin "2") (pinfunction "G_2") (pintype "passive"))
      (node (ref "R49") (pin "2") (pinfunction "2_2") (pintype "passive"))
      (node (ref "R52") (pin "2") (pinfunction "2_2") (pintype "passive"))
    )
    (net (code "57") (name "Net-(Q10-G)") (class "Default")
      (node (ref "Q10") (pin "2") (pinfunction "G_2") (pintype "passive"))
      (node (ref "Q9") (pin "2") (pinfunction "G_2") (pintype "passive"))
      (node (ref "R50") (pin "2") (pinfunction "2_2") (pintype "passive"))
      (node (ref "R53") (pin "2") (pinfunction "2_2") (pintype "passive"))
    )
    (net (code "58") (name "Net-(Q11-G)") (class "Default")
      (node (ref "Q11") (pin "2") (pinfunction "G_2") (pintype "passive"))
      (node (ref "Q12") (pin "2") (pinfunction "G_2") (pintype "passive"))
      (node (ref "R51") (pin "2") (pinfunction "2_2") (pintype "passive"))
      (node (ref "R54") (pin "2") (pinfunction "2_2") (pintype "passive"))
    )
    (net (code "59") (name "Net-(R7-Pad2)") (class "Default")
      (node (ref "R7") (pin "2") (pinfunction "2_2") (pintype "passive"))
      (node (ref "RUN1") (pin "1") (pinfunction "1_1") (pintype "passive"))
    )
    (net (code "60") (name "Net-(R19-Pad1)") (class "Default")
      (node (ref "R19") (pin "1") (pinfunction "1_1") (pintype "passive"))
      (node (ref "SIGIN") (pin "1") (pinfunction "1_1") (pintype "passive"))
    )
    (net (code "61") (name "Net-(R20-Pad1)") (class "Default")
      (node (ref "R20") (pin "1") (pinfunction "1_1") (pintype "passive"))
      (node (ref "SIGIN") (pin "2") (pinfunction "2_2") (pintype "passive"))
    )
    (net (code "62") (name "Net-(R30-Pad2)") (class "Default")
      (node (ref "R30") (pin "2") (pinfunction "2_2") (pintype "passive"))
      (node (ref "SIGIN") (pin "5") (pinfunction "5_5") (pintype "passive"))
    )
    (net (code "63") (name "Net-(R31-Pad1)") (class "Default")
      (node (ref "R31") (pin "1") (pinfunction "1_1") (pintype "passive"))
      (node (ref "SIGIN") (pin "6") (pinfunction "6_6") (pintype "passive"))
    )
    (net (code "64") (name "Net-(R34-Pad1)") (class "Default")
      (node (ref "R34") (pin "1") (pinfunction "1_1") (pintype "passive"))
      (node (ref "R36") (pin "2") (pinfunction "2_2") (pintype "passive"))
      (node (ref "R37") (pin "1") (pinfunction "1_1") (pintype "passive"))
    )
    (net (code "65") (name "Net-(R35-Pad1)") (class "Default")
      (node (ref "R35") (pin "1") (pinfunction "1_1") (pintype "passive"))
      (node (ref "R38") (pin "2") (pinfunction "2_2") (pintype "passive"))
      (node (ref "R39") (pin "1") (pinfunction "1_1") (pintype "passive"))
    )
    (net (code "66") (name "Net-(U1-EN)") (class "Default")
      (node (ref "R3") (pin "1") (pinfunction "1_1") (pintype "passive"))
      (node (ref "U1") (pin "2") (pinfunction "EN_2") (pintype "passive"))
    )
    (net (code "67") (name "Net-(U1-FB)") (class "Default")
      (node (ref "R4") (pin "1") (pinfunction "1_1") (pintype "passive"))
      (node (ref "R6") (pin "1") (pinfunction "1_1") (pintype "passive"))
      (node (ref "U1") (pin "1") (pinfunction "FB_1") (pintype "passive"))
    )
    (net (code "68") (name "Net-(U2-VB1)") (class "Default")
      (node (ref "C11") (pin "1") (pinfunction "1_1") (pintype "passive"))
      (node (ref "U2") (pin "48") (pinfunction "VB1_48") (pintype "passive"))
    )
    (net (code "69") (name "Net-(U2-VB2)") (class "Default")
      (node (ref "C12") (pin "1") (pinfunction "1_1") (pintype "passive"))
      (node (ref "U2") (pin "44") (pinfunction "VB2_44") (pintype "passive"))
    )
    (net (code "70") (name "Net-(U2-VB3)") (class "Default")
      (node (ref "C13") (pin "1") (pinfunction "1_1") (pintype "passive"))
      (node (ref "U2") (pin "40") (pinfunction "VB3_40") (pintype "passive"))
    )
    (net (code "71") (name "VCC5V") (class "Default")
      (node (ref "C15") (pin "1") (pinfunction "1_1") (pintype "passive"))
      (node (ref "C16") (pin "2") (pinfunction "2_2") (pintype "passive"))
      (node (ref "C17") (pin "2") (pinfunction "2_2") (pintype "passive"))
      (node (ref "C18") (pin "2") (pinfunction "2_2") (pintype "passive"))
      (node (ref "D4") (pin "K") (pinfunction "K_K") (pintype "passive"))
      (node (ref "ENABLE1") (pin "3") (pintype "passive"))
      (node (ref "Hall") (pin "6") (pinfunction "6_6") (pintype "passive"))
      (node (ref "R1") (pin "1") (pinfunction "1_1") (pintype "passive"))
      (node (ref "R12") (pin "2") (pinfunction "2_2") (pintype "passive"))
      (node (ref "R13") (pin "2") (pinfunction "2_2") (pintype "passive"))
      (node (ref "R14") (pin "2") (pinfunction "2_2") (pintype "passive"))
      (node (ref "R15") (pin "2") (pinfunction "2_2") (pintype "passive"))
      (node (ref "R2") (pin "1") (pinfunction "1_1") (pintype "passive"))
      (node (ref "R36") (pin "1") (pinfunction "1_1") (pintype "passive"))
      (node (ref "R38") (pin "1") (pinfunction "1_1") (pintype "passive"))
      (node (ref "R59") (pin "2") (pinfunction "2_2") (pintype "passive"))
      (node (ref "R7") (pin "1") (pinfunction "1_1") (pintype "passive"))
      (node (ref "R8") (pin "1") (pinfunction "1_1") (pintype "passive"))
      (node (ref "U2") (pin "23") (pinfunction "VDDIO_23") (pintype "passive"))
      (node (ref "U2") (pin "3") (pinfunction "VREG5/VDDIO_3") (pintype "passive"))
      (node (ref "U2") (pin "9") (pinfunction "VDDIO/VDDA_9") (pintype "passive"))
    )
    (net (code "72") (name "VCC12V") (class "Default")
      (node (ref "C2") (pin "1") (pinfunction "1_1") (pintype "passive"))
      (node (ref "C3") (pin "1") (pinfunction "1_1") (pintype "passive"))
      (node (ref "C4") (pin "1") (pinfunction "1_1") (pintype "passive"))
      (node (ref "D1") (pin "K") (pinfunction "K_K") (pintype "passive"))
      (node (ref "D2") (pin "K") (pinfunction "K_K") (pintype "passive"))
      (node (ref "D3") (pin "K") (pinfunction "K_K") (pintype "passive"))
      (node (ref "DCIN") (pin "1") (pinfunction "1_1") (pintype "passive"))
      (node (ref "Q1") (pin "1") (pinfunction "D_1") (pintype "passive"))
      (node (ref "Q2") (pin "1") (pinfunction "D_1") (pintype "passive"))
      (node (ref "Q3") (pin "1") (pinfunction "D_1") (pintype "passive"))
      (node (ref "Q4") (pin "1") (pinfunction "D_1") (pintype "passive"))
      (node (ref "Q5") (pin "1") (pinfunction "D_1") (pintype "passive"))
      (node (ref "Q6") (pin "1") (pinfunction "D_1") (pintype "passive"))
      (node (ref "R3") (pin "2") (pinfunction "2_2") (pintype "passive"))
      (node (ref "R4") (pin "2") (pinfunction "2_2") (pintype "passive"))
      (node (ref "U1") (pin "4") (pinfunction "IN_4") (pintype "passive"))
      (node (ref "U1") (pin "5") (pinfunction "VCC_5") (pintype "passive"))
    )
    (net (code "73") (name "VCC12VO") (class "Default")
      (node (ref "C1") (pin "1") (pinfunction "1_1") (pintype "passive"))
      (node (ref "C14") (pin "2") (pinfunction "2_2") (pintype "passive"))
      (node (ref "R5") (pin "1") (pinfunction "1_1") (pintype "passive"))
      (node (ref "U1") (pin "3") (pinfunction "OUT_3") (pintype "passive"))
      (node (ref "U2") (pin "2") (pinfunction "VCC_2") (pintype "passive"))
    )
    (net (code "74") (name "unconnected-(SW-Pad6)") (class "Default")
      (node (ref "SW") (pin "6") (pinfunction "6_6") (pintype "passive+no_connect"))
    )
    (net (code "75") (name "unconnected-(SW-Pad8)") (class "Default")
      (node (ref "SW") (pin "8") (pinfunction "8_8") (pintype "passive+no_connect"))
    )
  )
)
